# Taciturn_Fuzz.net
KiCad netlist of a schematic drawn in EAGLE
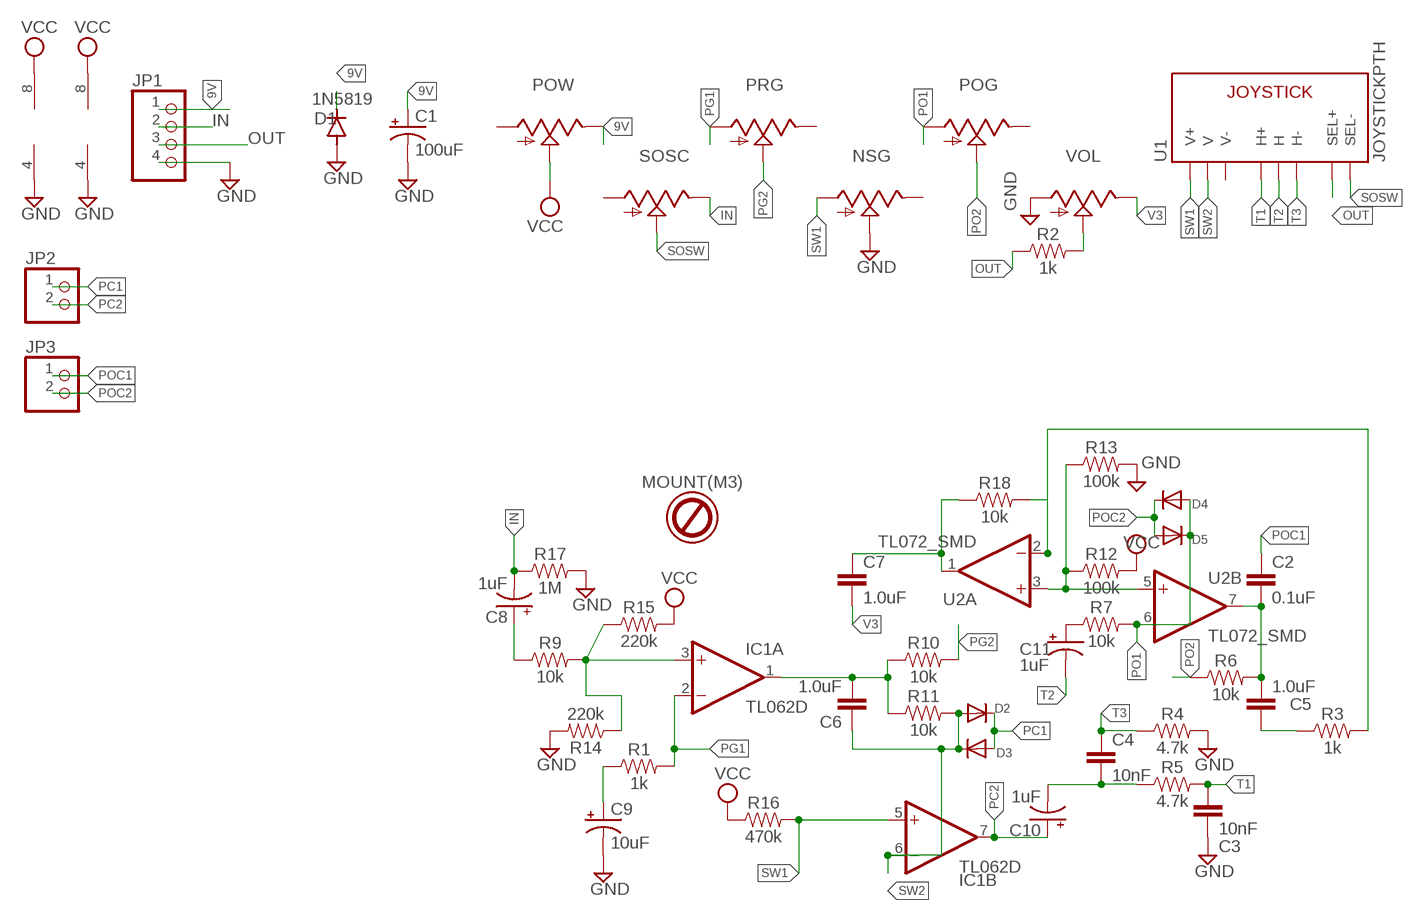
[diagram p0: schematic, sheet 1]

(export (version "E")
  (design (tool "Eeschema 10.0.6"))
  (components
    (comp (ref "C1")
      (value "100uF")
      (footprint "eagle-import:PAN_B_SMD+THRU")
      (libsource (lib "eagle-import") (part "CAP_SMD+THRUPAN_B"))
    )
    (comp (ref "C2")
      (value "0.1uF")
      (footprint "eagle-import:0603")
      (libsource (lib "eagle-import") (part "0.1UF-0603-25V-(+80/-20%)"))
    )
    (comp (ref "C3")
      (value "10nF")
      (footprint "eagle-import:0603")
      (libsource (lib "eagle-import") (part "10NF-0603-50V-10%"))
    )
    (comp (ref "C4")
      (value "10nF")
      (footprint "eagle-import:0603")
      (libsource (lib "eagle-import") (part "10NF-0603-50V-10%"))
    )
    (comp (ref "C5")
      (value "1.0uF")
      (footprint "eagle-import:0603")
      (libsource (lib "eagle-import") (part "1.0UF-0603-16V-10%"))
    )
    (comp (ref "C6")
      (value "1.0uF")
      (footprint "eagle-import:0603")
      (libsource (lib "eagle-import") (part "1.0UF-0603-16V-10%"))
    )
    (comp (ref "C7")
      (value "1.0uF")
      (footprint "eagle-import:0603")
      (libsource (lib "eagle-import") (part "1.0UF-0603-16V-10%"))
    )
    (comp (ref "C8")
      (value "1uF")
      (footprint "eagle-import:PAN_B_SMD+THRU")
      (libsource (lib "eagle-import") (part "CAP_SMD+THRUPAN_B"))
    )
    (comp (ref "C9")
      (value "10uF")
      (footprint "eagle-import:PAN_B_SMD+THRU")
      (libsource (lib "eagle-import") (part "CAP_SMD+THRUPAN_B"))
    )
    (comp (ref "C10")
      (value "1uF")
      (footprint "eagle-import:PAN_B_SMD+THRU")
      (libsource (lib "eagle-import") (part "CAP_SMD+THRUPAN_B"))
    )
    (comp (ref "C11")
      (value "1uF")
      (footprint "eagle-import:PAN_B_SMD+THRU")
      (libsource (lib "eagle-import") (part "CAP_SMD+THRUPAN_B"))
    )
    (comp (ref "D1")
      (value "1N5819")
      (footprint "eagle-import:SOD123")
      (libsource (lib "eagle-import") (part "DIODE-SOD123"))
    )
    (comp (ref "D2")
      (value "DIODESMA")
      (footprint "eagle-import:SMADIODE")
      (libsource (lib "eagle-import") (part "DIODESMA"))
    )
    (comp (ref "D3")
      (value "DIODESMA")
      (footprint "eagle-import:SMADIODE")
      (libsource (lib "eagle-import") (part "DIODESMA"))
    )
    (comp (ref "D4")
      (value "DIODESMA")
      (footprint "eagle-import:SMADIODE")
      (libsource (lib "eagle-import") (part "DIODESMA"))
    )
    (comp (ref "D5")
      (value "DIODESMA")
      (footprint "eagle-import:SMADIODE")
      (libsource (lib "eagle-import") (part "DIODESMA"))
    )
    (comp (ref "IC1")
      (value "TL062D")
      (footprint "eagle-import:SO08")
      (libsource (lib "eagle-import") (part "TL062D"))
    )
    (comp (ref "JP1")
      (value "PINHD-1X4")
      (footprint "eagle-import:1X04")
      (libsource (lib "eagle-import") (part "PINHD-1X4"))
    )
    (comp (ref "JP2")
      (value "PINHD-1X2")
      (footprint "eagle-import:1X02")
      (libsource (lib "eagle-import") (part "PINHD-1X2"))
    )
    (comp (ref "JP3")
      (value "PINHD-1X2")
      (footprint "eagle-import:1X02")
      (libsource (lib "eagle-import") (part "PINHD-1X2"))
    )
    (comp (ref "NSG")
      (value "9MM_SNAP-IN_POT_")
      (footprint "eagle-import:9MM_SNAP-IN_POT")
      (libsource (lib "eagle-import") (part "9MM_SNAP-IN_POT_"))
    )
    (comp (ref "O1")
      (value "MOUNT(M3)")
      (footprint "eagle-import:HOLE-3.5MM")
      (libsource (lib "eagle-import") (part "MOUNT(?)M3"))
    )
    (comp (ref "POG")
      (value "9MM_SNAP-IN_POT_")
      (footprint "eagle-import:9MM_SNAP-IN_POT")
      (libsource (lib "eagle-import") (part "9MM_SNAP-IN_POT_"))
    )
    (comp (ref "POW")
      (value "9MM_SNAP-IN_POT_")
      (footprint "eagle-import:9MM_SNAP-IN_POT")
      (libsource (lib "eagle-import") (part "9MM_SNAP-IN_POT_"))
    )
    (comp (ref "PRG")
      (value "9MM_SNAP-IN_POT_")
      (footprint "eagle-import:9MM_SNAP-IN_POT")
      (libsource (lib "eagle-import") (part "9MM_SNAP-IN_POT_"))
    )
    (comp (ref "R1")
      (value "1k")
      (footprint "eagle-import:0603")
      (libsource (lib "eagle-import") (part "1KOHM-0603-1/10W-1%"))
    )
    (comp (ref "R2")
      (value "1k")
      (footprint "eagle-import:0603")
      (libsource (lib "eagle-import") (part "1KOHM-0603-1/10W-1%"))
    )
    (comp (ref "R3")
      (value "1k")
      (footprint "eagle-import:0603")
      (libsource (lib "eagle-import") (part "1KOHM-0603-1/10W-1%"))
    )
    (comp (ref "R4")
      (value "4.7k")
      (footprint "eagle-import:0603")
      (libsource (lib "eagle-import") (part "4.7KOHM-0603-1/10W-1%"))
    )
    (comp (ref "R5")
      (value "4.7k")
      (footprint "eagle-import:0603")
      (libsource (lib "eagle-import") (part "4.7KOHM-0603-1/10W-1%"))
    )
    (comp (ref "R6")
      (value "10k")
      (footprint "eagle-import:0603")
      (libsource (lib "eagle-import") (part "10KOHM-0603-1/10W-1%"))
    )
    (comp (ref "R7")
      (value "10k")
      (footprint "eagle-import:0603")
      (libsource (lib "eagle-import") (part "10KOHM-0603-1/10W-1%"))
    )
    (comp (ref "R9")
      (value "10k")
      (footprint "eagle-import:0603")
      (libsource (lib "eagle-import") (part "10KOHM-0603-1/10W-1%"))
    )
    (comp (ref "R10")
      (value "10k")
      (footprint "eagle-import:0603")
      (libsource (lib "eagle-import") (part "10KOHM-0603-1/10W-1%"))
    )
    (comp (ref "R11")
      (value "10k")
      (footprint "eagle-import:0603")
      (libsource (lib "eagle-import") (part "10KOHM-0603-1/10W-1%"))
    )
    (comp (ref "R12")
      (value "100k")
      (footprint "eagle-import:0603")
      (libsource (lib "eagle-import") (part "100KOHM-0603-1/10W-1%"))
    )
    (comp (ref "R13")
      (value "100k")
      (footprint "eagle-import:0603")
      (libsource (lib "eagle-import") (part "100KOHM-0603-1/10W-1%"))
    )
    (comp (ref "R14")
      (value "220k")
      (footprint "eagle-import:0603")
      (libsource (lib "eagle-import") (part "220KOHM-0603-1/10W-1%"))
    )
    (comp (ref "R15")
      (value "220k")
      (footprint "eagle-import:0603")
      (libsource (lib "eagle-import") (part "220KOHM-0603-1/10W-1%"))
    )
    (comp (ref "R16")
      (value "470k")
      (footprint "eagle-import:0603")
      (libsource (lib "eagle-import") (part "470OHM-0603-1/10W-1%"))
    )
    (comp (ref "R17")
      (value "1M")
      (footprint "eagle-import:0603")
      (libsource (lib "eagle-import") (part "1MOHM-0603-1/4W-5%"))
    )
    (comp (ref "R18")
      (value "10k")
      (footprint "eagle-import:0603")
      (libsource (lib "eagle-import") (part "10KOHM-0603-1/10W-1%"))
    )
    (comp (ref "SOSC")
      (value "9MM_SNAP-IN_POT_")
      (footprint "eagle-import:9MM_SNAP-IN_POT")
      (libsource (lib "eagle-import") (part "9MM_SNAP-IN_POT_"))
    )
    (comp (ref "U1")
      (value "JOYSTICKPTH")
      (footprint "eagle-import:JOYSTICK")
      (libsource (lib "eagle-import") (part "JOYSTICKPTH"))
    )
    (comp (ref "U2")
      (value "TL072_SMD")
      (footprint "eagle-import:SO08")
      (libsource (lib "eagle-import") (part "TL072_SMD"))
    )
    (comp (ref "VOL")
      (value "9MM_SNAP-IN_POT_")
      (footprint "eagle-import:9MM_SNAP-IN_POT")
      (libsource (lib "eagle-import") (part "9MM_SNAP-IN_POT_"))
    )
  )
  (nets
    (net (code "1") (name "9V") (class "Default")
      (node (ref "C1") (pin "+") (pinfunction "+_+") (pintype "passive"))
      (node (ref "C1") (pin "++") (pinfunction "+_++") (pintype "passive"))
      (node (ref "D1") (pin "C") (pinfunction "C_C") (pintype "passive"))
      (node (ref "JP1") (pin "1") (pinfunction "1_1") (pintype "passive"))
      (node (ref "POW") (pin "3") (pinfunction "E_3") (pintype "passive"))
    )
    (net (code "2") (name "GND") (class "Default")
      (node (ref "C1") (pin "-") (pinfunction "-_-") (pintype "passive"))
      (node (ref "C1") (pin "--") (pinfunction "-_--") (pintype "passive"))
      (node (ref "C3") (pin "2") (pinfunction "2_2") (pintype "passive"))
      (node (ref "C9") (pin "-") (pinfunction "-_-") (pintype "passive"))
      (node (ref "C9") (pin "--") (pinfunction "-_--") (pintype "passive"))
      (node (ref "D1") (pin "A") (pinfunction "A_A") (pintype "passive"))
      (node (ref "IC1") (pin "4") (pinfunction "V-_4") (pintype "power_in"))
      (node (ref "JP1") (pin "4") (pinfunction "4_4") (pintype "passive"))
      (node (ref "NSG") (pin "2") (pinfunction "S_2") (pintype "passive"))
      (node (ref "R13") (pin "2") (pinfunction "2_2") (pintype "passive"))
      (node (ref "R14") (pin "2") (pinfunction "2_2") (pintype "passive"))
      (node (ref "R17") (pin "2") (pinfunction "2_2") (pintype "passive"))
      (node (ref "R4") (pin "2") (pinfunction "2_2") (pintype "passive"))
      (node (ref "U2") (pin "4") (pinfunction "V-_4") (pintype "power_in"))
      (node (ref "VOL") (pin "1") (pinfunction "A_1") (pintype "passive"))
    )
    (net (code "3") (name "IN") (class "Default")
      (node (ref "C8") (pin "-") (pinfunction "-_-") (pintype "passive"))
      (node (ref "C8") (pin "--") (pinfunction "-_--") (pintype "passive"))
      (node (ref "JP1") (pin "2") (pinfunction "2_2") (pintype "passive"))
      (node (ref "R17") (pin "1") (pinfunction "1_1") (pintype "passive"))
      (node (ref "SOSC") (pin "3") (pinfunction "E_3") (pintype "passive"))
    )
    (net (code "4") (name "Net-(C5-Pad2)") (class "Default")
      (node (ref "C5") (pin "2") (pinfunction "2_2") (pintype "passive"))
      (node (ref "R3") (pin "1") (pinfunction "1_1") (pintype "passive"))
    )
    (net (code "5") (name "Net-(C8-+-Pad++)") (class "Default")
      (node (ref "C8") (pin "+") (pinfunction "+_+") (pintype "passive"))
      (node (ref "C8") (pin "++") (pinfunction "+_++") (pintype "passive"))
      (node (ref "R9") (pin "1") (pinfunction "1_1") (pintype "passive"))
    )
    (net (code "6") (name "Net-(C9-+-Pad++)") (class "Default")
      (node (ref "C9") (pin "+") (pinfunction "+_+") (pintype "passive"))
      (node (ref "C9") (pin "++") (pinfunction "+_++") (pintype "passive"))
      (node (ref "R1") (pin "1") (pinfunction "1_1") (pintype "passive"))
    )
    (net (code "7") (name "Net-(C10---Pad--)") (class "Default")
      (node (ref "C10") (pin "-") (pinfunction "-_-") (pintype "passive"))
      (node (ref "C10") (pin "--") (pinfunction "-_--") (pintype "passive"))
      (node (ref "C4") (pin "2") (pinfunction "2_2") (pintype "passive"))
      (node (ref "R5") (pin "1") (pinfunction "1_1") (pintype "passive"))
    )
    (net (code "8") (name "Net-(C11-+-Pad++)") (class "Default")
      (node (ref "C11") (pin "+") (pinfunction "+_+") (pintype "passive"))
      (node (ref "C11") (pin "++") (pinfunction "+_++") (pintype "passive"))
      (node (ref "R7") (pin "1") (pinfunction "1_1") (pintype "passive"))
    )
    (net (code "9") (name "Net-(IC1A-+IN)") (class "Default")
      (node (ref "IC1") (pin "3") (pinfunction "+IN_3") (pintype "input"))
      (node (ref "R14") (pin "1") (pinfunction "1_1") (pintype "passive"))
      (node (ref "R15") (pin "1") (pinfunction "1_1") (pintype "passive"))
      (node (ref "R9") (pin "2") (pinfunction "2_2") (pintype "passive"))
    )
    (net (code "10") (name "Net-(IC1A-OUT)") (class "Default")
      (node (ref "C6") (pin "2") (pinfunction "2_2") (pintype "passive"))
      (node (ref "IC1") (pin "1") (pinfunction "OUT_1") (pintype "output"))
      (node (ref "R10") (pin "1") (pinfunction "1_1") (pintype "passive"))
      (node (ref "R11") (pin "1") (pinfunction "1_1") (pintype "passive"))
    )
    (net (code "11") (name "Net-(U2A-+IN)") (class "Default")
      (node (ref "R12") (pin "1") (pinfunction "1_1") (pintype "passive"))
      (node (ref "R13") (pin "1") (pinfunction "1_1") (pintype "passive"))
      (node (ref "U2") (pin "3") (pinfunction "+IN_3") (pintype "input"))
      (node (ref "U2") (pin "5") (pinfunction "+IN_5") (pintype "input"))
    )
    (net (code "12") (name "Net-(U2A--IN)") (class "Default")
      (node (ref "R18") (pin "2") (pinfunction "2_2") (pintype "passive"))
      (node (ref "R3") (pin "2") (pinfunction "2_2") (pintype "passive"))
      (node (ref "U2") (pin "2") (pinfunction "-IN_2") (pintype "input"))
    )
    (net (code "13") (name "Net-(U2A-OUT)") (class "Default")
      (node (ref "C7") (pin "1") (pinfunction "1_1") (pintype "passive"))
      (node (ref "R18") (pin "1") (pinfunction "1_1") (pintype "passive"))
      (node (ref "U2") (pin "1") (pinfunction "OUT_1") (pintype "output"))
    )
    (net (code "14") (name "Net-(U2B-OUT)") (class "Default")
      (node (ref "C2") (pin "2") (pinfunction "2_2") (pintype "passive"))
      (node (ref "C5") (pin "1") (pinfunction "1_1") (pintype "passive"))
      (node (ref "R6") (pin "2") (pinfunction "2_2") (pintype "passive"))
      (node (ref "U2") (pin "7") (pinfunction "OUT_7") (pintype "output"))
    )
    (net (code "15") (name "Net-(VOL-S)") (class "Default")
      (node (ref "R2") (pin "2") (pinfunction "2_2") (pintype "passive"))
      (node (ref "VOL") (pin "2") (pinfunction "S_2") (pintype "passive"))
    )
    (net (code "16") (name "OUT") (class "Default")
      (node (ref "JP1") (pin "3") (pinfunction "3_3") (pintype "passive"))
      (node (ref "R2") (pin "1") (pinfunction "1_1") (pintype "passive"))
      (node (ref "U1") (pin "B1A") (pinfunction "SEL+_B1A") (pintype "bidirectional"))
    )
    (net (code "17") (name "PC1") (class "Default")
      (node (ref "D2") (pin "C") (pinfunction "C_C") (pintype "passive"))
      (node (ref "D3") (pin "A") (pinfunction "A_A") (pintype "passive"))
      (node (ref "JP2") (pin "1") (pinfunction "1_1") (pintype "passive"))
    )
    (net (code "18") (name "PC2") (class "Default")
      (node (ref "C10") (pin "+") (pinfunction "+_+") (pintype "passive"))
      (node (ref "C10") (pin "++") (pinfunction "+_++") (pintype "passive"))
      (node (ref "IC1") (pin "7") (pinfunction "OUT_7") (pintype "output"))
      (node (ref "JP2") (pin "2") (pinfunction "2_2") (pintype "passive"))
    )
    (net (code "19") (name "PG1") (class "Default")
      (node (ref "IC1") (pin "2") (pinfunction "-IN_2") (pintype "input"))
      (node (ref "PRG") (pin "1") (pinfunction "A_1") (pintype "passive"))
      (node (ref "R1") (pin "2") (pinfunction "2_2") (pintype "passive"))
    )
    (net (code "20") (name "PG2") (class "Default")
      (node (ref "PRG") (pin "2") (pinfunction "S_2") (pintype "passive"))
      (node (ref "R10") (pin "2") (pinfunction "2_2") (pintype "passive"))
    )
    (net (code "21") (name "PO1") (class "Default")
      (node (ref "D4") (pin "A") (pinfunction "A_A") (pintype "passive"))
      (node (ref "D5") (pin "C") (pinfunction "C_C") (pintype "passive"))
      (node (ref "POG") (pin "1") (pinfunction "A_1") (pintype "passive"))
      (node (ref "R7") (pin "2") (pinfunction "2_2") (pintype "passive"))
      (node (ref "U2") (pin "6") (pinfunction "-IN_6") (pintype "input"))
    )
    (net (code "22") (name "PO2") (class "Default")
      (node (ref "POG") (pin "2") (pinfunction "S_2") (pintype "passive"))
      (node (ref "R6") (pin "1") (pinfunction "1_1") (pintype "passive"))
    )
    (net (code "23") (name "POC1") (class "Default")
      (node (ref "C2") (pin "1") (pinfunction "1_1") (pintype "passive"))
      (node (ref "JP3") (pin "1") (pinfunction "1_1") (pintype "passive"))
    )
    (net (code "24") (name "POC2") (class "Default")
      (node (ref "D4") (pin "C") (pinfunction "C_C") (pintype "passive"))
      (node (ref "D5") (pin "A") (pinfunction "A_A") (pintype "passive"))
      (node (ref "JP3") (pin "2") (pinfunction "2_2") (pintype "passive"))
    )
    (net (code "25") (name "SOSW") (class "Default")
      (node (ref "SOSC") (pin "2") (pinfunction "S_2") (pintype "passive"))
      (node (ref "U1") (pin "B2A") (pinfunction "SEL-_B2A") (pintype "bidirectional"))
    )
    (net (code "26") (name "SW1") (class "Default")
      (node (ref "IC1") (pin "5") (pinfunction "+IN_5") (pintype "input"))
      (node (ref "NSG") (pin "1") (pinfunction "A_1") (pintype "passive"))
      (node (ref "R16") (pin "2") (pinfunction "2_2") (pintype "passive"))
      (node (ref "U1") (pin "V1") (pinfunction "V+_V1") (pintype "bidirectional"))
    )
    (net (code "27") (name "SW2") (class "Default")
      (node (ref "C6") (pin "1") (pinfunction "1_1") (pintype "passive"))
      (node (ref "D2") (pin "A") (pinfunction "A_A") (pintype "passive"))
      (node (ref "D3") (pin "C") (pinfunction "C_C") (pintype "passive"))
      (node (ref "IC1") (pin "6") (pinfunction "-IN_6") (pintype "input"))
      (node (ref "R11") (pin "2") (pinfunction "2_2") (pintype "passive"))
      (node (ref "U1") (pin "V2") (pinfunction "V_V2") (pintype "bidirectional"))
    )
    (net (code "28") (name "T1") (class "Default")
      (node (ref "C3") (pin "1") (pinfunction "1_1") (pintype "passive"))
      (node (ref "R5") (pin "2") (pinfunction "2_2") (pintype "passive"))
      (node (ref "U1") (pin "H1") (pinfunction "H+_H1") (pintype "bidirectional"))
    )
    (net (code "29") (name "T2") (class "Default")
      (node (ref "C11") (pin "-") (pinfunction "-_-") (pintype "passive"))
      (node (ref "C11") (pin "--") (pinfunction "-_--") (pintype "passive"))
      (node (ref "U1") (pin "H2") (pinfunction "H_H2") (pintype "bidirectional"))
    )
    (net (code "30") (name "T3") (class "Default")
      (node (ref "C4") (pin "1") (pinfunction "1_1") (pintype "passive"))
      (node (ref "R4") (pin "1") (pinfunction "1_1") (pintype "passive"))
      (node (ref "U1") (pin "H3") (pinfunction "H-_H3") (pintype "bidirectional"))
    )
    (net (code "31") (name "V3") (class "Default")
      (node (ref "C7") (pin "2") (pinfunction "2_2") (pintype "passive"))
      (node (ref "VOL") (pin "3") (pinfunction "E_3") (pintype "passive"))
    )
    (net (code "32") (name "VCC") (class "Default")
      (node (ref "IC1") (pin "8") (pinfunction "V+_8") (pintype "power_in"))
      (node (ref "POW") (pin "2") (pinfunction "S_2") (pintype "passive"))
      (node (ref "R12") (pin "2") (pinfunction "2_2") (pintype "passive"))
      (node (ref "R15") (pin "2") (pinfunction "2_2") (pintype "passive"))
      (node (ref "R16") (pin "1") (pinfunction "1_1") (pintype "passive"))
      (node (ref "U2") (pin "8") (pinfunction "V+_8") (pintype "power_in"))
    )
    (net (code "33") (name "unconnected-(NSG-E-Pad3)") (class "Default")
      (node (ref "NSG") (pin "3") (pinfunction "E_3") (pintype "passive"))
    )
    (net (code "34") (name "unconnected-(O1-P$1-PadMNT)") (class "Default")
      (node (ref "O1") (pin "MNT") (pinfunction "P$1_MNT") (pintype "bidirectional"))
    )
    (net (code "35") (name "unconnected-(POG-E-Pad3)") (class "Default")
      (node (ref "POG") (pin "3") (pinfunction "E_3") (pintype "passive"))
    )
    (net (code "36") (name "unconnected-(POW-A-Pad1)") (class "Default")
      (node (ref "POW") (pin "1") (pinfunction "A_1") (pintype "passive"))
    )
    (net (code "37") (name "unconnected-(PRG-E-Pad3)") (class "Default")
      (node (ref "PRG") (pin "3") (pinfunction "E_3") (pintype "passive"))
    )
    (net (code "38") (name "unconnected-(SOSC-A-Pad1)") (class "Default")
      (node (ref "SOSC") (pin "1") (pinfunction "A_1") (pintype "passive"))
    )
    (net (code "39") (name "unconnected-(U1-V--PadV3)") (class "Default")
      (node (ref "U1") (pin "V3") (pinfunction "V-_V3") (pintype "bidirectional"))
    )
  )
)
